# 12V_Buck.net
KiCad netlist of a schematic drawn in Altium Designer
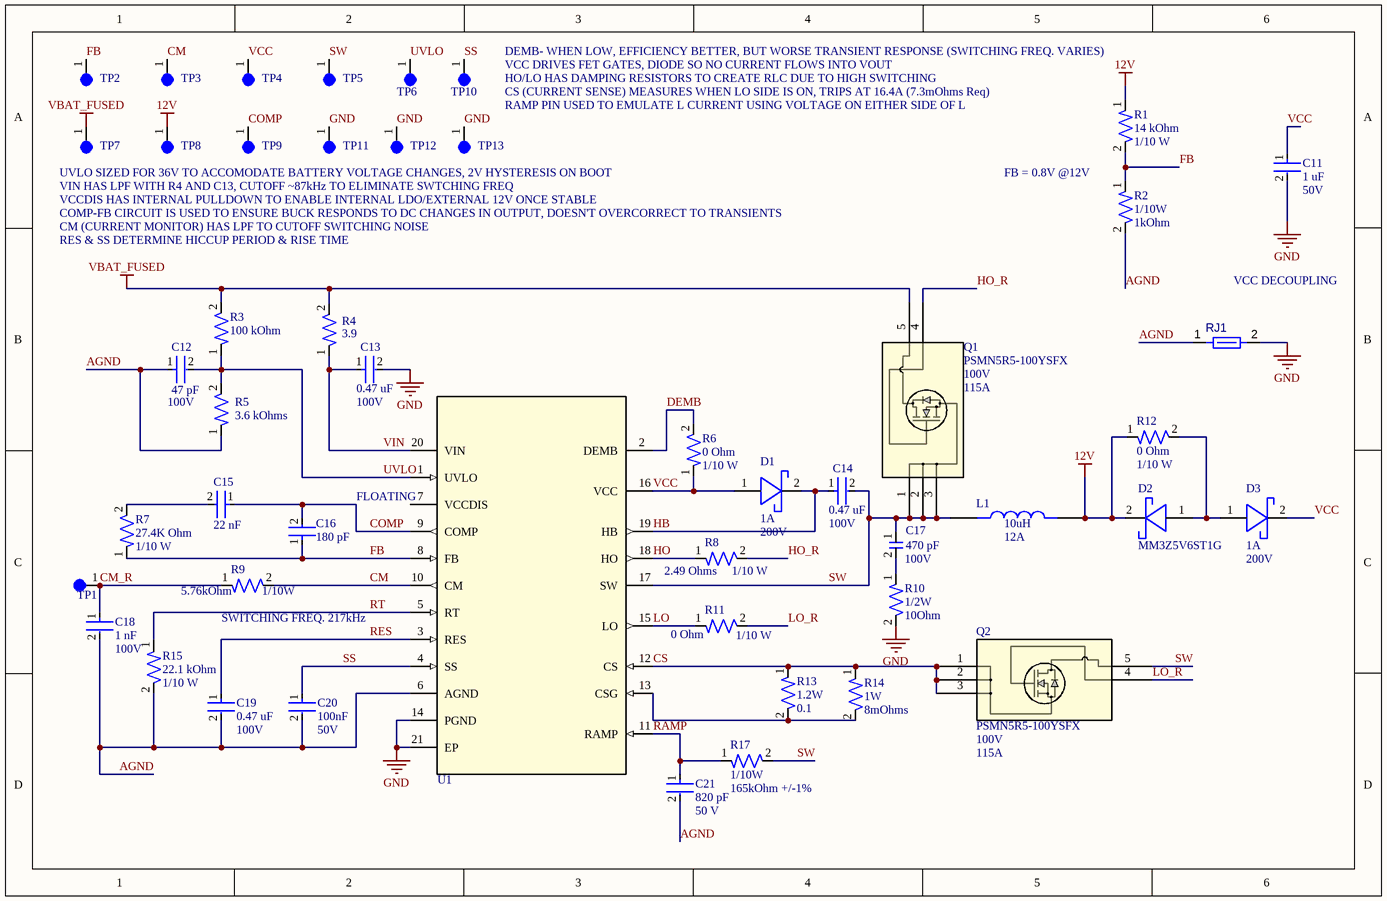
[diagram p0: 12V_Buck.SchDoc]

(export (version "E")
  (design (tool "Eeschema 10.0.6"))
  (components
    (comp (ref "C11")
      (value "UMK107AB7105KA-T")
      (footprint "CAP-0603")
      (description "1 µF ±10% 50V Ceramic Capacitor X7R 0603 (1608 Metric)")
      (fields (field (name "CAPACITANCE") "1 uF") (field (name "VOLTAGE") "50V"))
      (libsource (lib "MasterLib") (part "CAP-1U-0002"))
    )
    (comp (ref "C12")
      (value "7447798111")
      (footprint "CAP-0603")
      (description "47 pF ±5% 100V Ceramic Capacitor C0G, NP0 0603 (1608 Metric)")
      (fields (field (name "CAPACITANCE") "47 pF") (field (name "VOLTAGE RATING") "100V"))
      (libsource (lib "MasterLib") (part "CAP-47P-0001"))
    )
    (comp (ref "C13")
      (value "KAM21KR72A474KL")
      (footprint "CAP-0805")
      (description "0.47 µF ±10% 100V Ceramic Capacitor X7R 0805 (2012 Metric)")
      (fields
        (field (name "TOLERANCE") "+/- 10%")
        (field (name "CAPACITANCE") "0.47 uF")
        (field (name "VOLTAGE") "100V")
      )
      (libsource (lib "MasterLib") (part "CAP-0.47U-0001"))
    )
    (comp (ref "C14")
      (value "KAM21KR72A474KL")
      (footprint "CAP-0805")
      (description "0.47 µF ±10% 100V Ceramic Capacitor X7R 0805 (2012 Metric)")
      (fields
        (field (name "TOLERANCE") "+/- 10%")
        (field (name "CAPACITANCE") "0.47 uF")
        (field (name "VOLTAGE") "100V")
      )
      (libsource (lib "MasterLib") (part "CAP-0.47U-0001"))
    )
    (comp (ref "C15")
      (value "C0603C223K3RAC7867")
      (footprint "CAP-0603")
      (description "0.022 µF ±10% 25V Ceramic Capacitor X7R 0603 (1608 Metric)")
      (fields (field (name "CAPACITANCE") "22 nF"))
      (libsource (lib "MasterLib") (part "CAP-22N-0001"))
    )
    (comp (ref "C16")
      (value "CC0603JRNPO9BN181")
      (footprint "CAP-0603")
      (description "180 pF ±5% 50V Ceramic Capacitor C0G, NP0 0603 (1608 Metric)")
      (fields
        (field (name "TOLERANCE") "+/- 10%")
        (field (name "CAPACITANCE") "180 pF")
        (field (name "VOLTAGE") "50V")
      )
      (libsource (lib "MasterLib") (part "CAP-180P-0001"))
    )
    (comp (ref "C17")
      (value "0603B471K101CT")
      (footprint "CAP-0603")
      (description "470 pF ±10% 100V Ceramic Capacitor X7R 0603 (1608 Metric)")
      (fields
        (field (name "TOLERANCE") "10%")
        (field (name "CAPACITANCE") "470 pF")
        (field (name "VOLTAGE") "100V")
      )
      (libsource (lib "MasterLib") (part "CAP-470P-0001"))
    )
    (comp (ref "C18")
      (value "C0603Y102K1RAC7867")
      (footprint "CAP-0603")
      (description "1000 pF ±10% 100V Ceramic Capacitor X7R 0603 (1608 Metric)")
      (fields (field (name "CAPACITANCE") "1 nF") (field (name "VOLTAGE") "100V"))
      (libsource (lib "MasterLib") (part "CAP-1N-0001"))
    )
    (comp (ref "C19")
      (value "KAM21KR72A474KL")
      (footprint "CAP-0805")
      (description "0.47 µF ±10% 100V Ceramic Capacitor X7R 0805 (2012 Metric)")
      (fields
        (field (name "TOLERANCE") "+/- 10%")
        (field (name "CAPACITANCE") "0.47 uF")
        (field (name "VOLTAGE") "100V")
      )
      (libsource (lib "MasterLib") (part "CAP-0.47U-0001"))
    )
    (comp (ref "C20")
      (value "CC0603KRX7R9BB104")
      (footprint "CAP-0603")
      (description "0.1 µF ±10% 50V Ceramic Capacitor X7R 0603 (1608 Metric)")
      (fields
        (field (name "MANUFACTURER PART NUMBER") "CC0603KRX7R0BB104")
        (field (name "MANUFACTURER") "YAGEO")
        (field (name "CAPACITANCE") "100nF")
        (field (name "VOLTAGE RATING") "50V")
      )
      (libsource (lib "MasterLib") (part "CAP-100N-0001"))
    )
    (comp (ref "C21")
      (value "C0603C821K5RACTU")
      (footprint "CAP-0603")
      (description "820 pF ±10% 50V Ceramic Capacitor X7R 0603 (1608 Metric)")
      (fields (field (name "CAPACITANCE") "820 pF") (field (name "VOLTAGE") "50 V"))
      (libsource (lib "JLC_25") (part "CAP-820P-0001"))
    )
    (comp (ref "D1")
      (value "SS1200")
      (footprint "SMA_DIO")
      (description "DIODE SCHOTTKY 200V 1A SMA")
      (fields (field (name "CURRENT RATING") "1A") (field (name "REVERSE VOLTAGE") "200V"))
      (libsource (lib "JLC_25") (part "DIO-SCHOTTKY-0004"))
    )
    (comp (ref "D2")
      (value "MM3Z5V6ST1G")
      (footprint "DIO_MM3Z3V0T1G - duplicate")
      (libsource (lib "MasterLib") (part "TESTDIOZ"))
    )
    (comp (ref "D3")
      (value "SS1200")
      (footprint "SMA_DIO")
      (description "DIODE SCHOTTKY 200V 1A SMA")
      (fields (field (name "CURRENT RATING") "1A") (field (name "REVERSE VOLTAGE") "200V"))
      (libsource (lib "JLC_25") (part "DIO-SCHOTTKY-0004"))
    )
    (comp (ref "L1")
      (value "10uH")
      (footprint "IND_SRP1265_BRN")
      (description "10 µH Shielded Inductor 12 A 16.5mOhm Max Nonstandard")
      (fields
        (field (name "MP") "SRP1265A-100M")
        (field (name "CURRENT") "12A")
        (field (name "Comment") "SRP1265WA-100M")
      )
      (libsource (lib "MasterLib") (part "IND-10U-0002"))
    )
    (comp (ref "Q1")
      (value "PSMN5R5-100YSFX")
      (footprint "LFPAK_SOT669_NEX")
      (description "N-Channel 100 V 115A (Tc) 238W (Tc) Surface Mount LFPAK56, Power-SO8")
      (fields
        (field (name "MANUFACTURER_PART_NUMBER") "TPH2R506PL")
        (field (name "VDSS") "100V")
        (field (name "DRAIN CURRENT") "115A")
      )
      (libsource (lib "") (part "NMOS-115A-0001_1"))
    )
    (comp (ref "Q2")
      (value "PSMN5R5-100YSFX")
      (footprint "LFPAK_SOT669_NEX")
      (description "N-Channel 100 V 115A (Tc) 238W (Tc) Surface Mount LFPAK56, Power-SO8")
      (fields
        (field (name "MANUFACTURER_PART_NUMBER") "TPH2R506PL")
        (field (name "VDSS") "100V")
        (field (name "DRAIN CURRENT") "115A")
      )
      (libsource (lib "MasterLib") (part "NMOS-115A-0001"))
    )
    (comp (ref "R1")
      (value "RC0603FR-0714KL")
      (footprint "RES-0603")
      (description "14 kOhms ±1% 0.1W, 1/10W Chip Resistor 0603 (1608 Metric) Moisture Resistant Thick Film")
      (fields
        (field (name "TOLERANCE") "+/- 1%")
        (field (name "RESISTANCE") "14 kOhm")
        (field (name "POWER") "1/10 W")
      )
      (libsource (lib "MasterLib") (part "RES-14K-0001"))
    )
    (comp (ref "R2")
      (value "RT0603FRE131KL")
      (footprint "RES-0603")
      (description "1 kOhms ±1% 0.1W, 1/10W Chip Resistor 0603 (1608 Metric) Thin Film")
      (fields
        (field (name "MANUFACTURER") "YAGEO")
        (field (name "POWER RATING") "1/10W")
        (field (name "RESISTANCE") "1kOhm")
      )
      (libsource (lib "MasterLib") (part "RES-1K-0002"))
    )
    (comp (ref "R3")
      (value "RC0603FR-07100KL")
      (footprint "RES-0603")
      (description "100 kOhms ±1% 0.1W, 1/10W Chip Resistor 0603 (1608 Metric) Moisture Resistant Thick Film")
      (fields
        (field (name "TOLERANCE") "+/- 1%")
        (field (name "RESISTANCE") "100 kOhm")
        (field (name "POWER") "1/10 W")
      )
      (libsource (lib "MasterLib") (part "RES-100K-0003"))
    )
    (comp (ref "R4")
      (value "RC0805FR-073R9L")
      (footprint "RES-0805")
      (description "3.9 Ohms ±1% 0.125W, 1/8W Chip Resistor 0805 (2012 Metric) Moisture Resistant Thick Film")
      (fields (field (name "PARAMETER 1") "3.9"))
      (libsource (lib "MasterLib") (part "RES-3.9-0001"))
    )
    (comp (ref "R5")
      (value "RC0603FR-073K6L")
      (footprint "RES-0603")
      (description "3.6 kOhms ±1% 0.1W, 1/10W Chip Resistor 0603 (1608 Metric) Moisture Resistant Thick Film")
      (fields (field (name "RESISTANCE") "3.6 kOhms") (field (name "POWER") "1/10 W"))
      (libsource (lib "MasterLib") (part "RES-3.6K-0001"))
    )
    (comp (ref "R6")
      (value "RMCF0603ZT0R00")
      (footprint "RES-0603")
      (description "0 Ohms Jumper 0.1W, 1/10W Chip Resistor 0603 (1608 Metric) Automotive AEC-Q200 Thick Film")
      (fields (field (name "RESISTANCE") "0 Ohm") (field (name "POWER") "1/10 W"))
      (libsource (lib "MasterLib") (part "RES-0-0001"))
    )
    (comp (ref "R7")
      (value "RC0603FR-0727K4L")
      (footprint "RES-0603")
      (description "27.4 kOhms ±1% 0.1W, 1/10W Chip Resistor 0603 (1608 Metric) Moisture Resistant Thick Film")
      (fields
        (field (name "JLC PART NUMBER") "C144778")
        (field (name "RESISTANCE") "27.4K Ohm")
        (field (name "POWER") "1/10 W")
      )
      (libsource (lib "MasterLib") (part "RES-27.4K-0001"))
    )
    (comp (ref "R8")
      (value "RC0603FR-072R49L")
      (footprint "RES-0603")
      (description "2.49 Ohms ±1% 0.1W, 1/10W Chip Resistor 0603 (1608 Metric) Moisture Resistant Thick Film")
      (fields (field (name "POWER") "1/10 W") (field (name "RESISTANCE") "2.49 Ohms"))
      (libsource (lib "MasterLib") (part "RES-2.49-0001"))
    )
    (comp (ref "R9")
      (value "ARG03FTC5761")
      (footprint "RES-0603")
      (fields
        (field (name "MANUFACTURER") "Viking Tech")
        (field (name "POWER RATING") "1/10W")
        (field (name "RESISTANCE") "5.76kOhm")
      )
      (libsource (lib "MasterLib") (part "RES-5.76K-0001"))
    )
    (comp (ref "R10")
      (value "SG73P1JTTD100J")
      (footprint "RES-0603")
      (fields
        (field (name "MANUFACTURER PART NUMBER") "RC0603FR-0710KP")
        (field (name "MANUFACTURER") "Vishay")
        (field (name "POWER RATING") "1/2W")
        (field (name "RESISTANCE") "10Ohm")
      )
      (libsource (lib "MasterLib") (part "RES-10-0001"))
    )
    (comp (ref "R11")
      (value "RMCF0603ZT0R00")
      (footprint "RES-0603")
      (description "0 Ohms Jumper 0.1W, 1/10W Chip Resistor 0603 (1608 Metric) Automotive AEC-Q200 Thick Film")
      (fields (field (name "RESISTANCE") "0 Ohm") (field (name "POWER") "1/10 W"))
      (libsource (lib "MasterLib") (part "RES-0-0001"))
    )
    (comp (ref "R12")
      (value "RMCF0603ZT0R00")
      (footprint "RES-0603")
      (description "0 Ohms Jumper 0.1W, 1/10W Chip Resistor 0603 (1608 Metric) Automotive AEC-Q200 Thick Film")
      (fields (field (name "RESISTANCE") "0 Ohm") (field (name "POWER") "1/10 W"))
      (libsource (lib "MasterLib") (part "RES-0-0001"))
    )
    (comp (ref "R13")
      (value "PE0508FRE070R1L")
      (footprint "RES-0805")
      (fields (field (name "POWER") "1.2W") (field (name "RESISTANCE") "0.1"))
      (libsource (lib "MasterLib") (part "RES-0.1-0001"))
    )
    (comp (ref "R14")
      (value "PE1206FKM470R008Z")
      (footprint "RES-1206")
      (description "8 mOhms ±1% 1W Chip Resistor 1206 (3216 Metric) Current Sense Metal Foil")
      (fields (field (name "POWER") "1W") (field (name "RESISTANCE") "8mOhms"))
      (libsource (lib "MasterLib") (part "RES-8mOhms-0001"))
    )
    (comp (ref "R15")
      (value "RC0603FR-0722K1L")
      (footprint "RES-0603")
      (description "22.1 kOhms ±1% 0.1W, 1/10W Chip Resistor 0603 (1608 Metric) Moisture Resistant Thick Film")
      (fields
        (field (name "TOLERANCE") "1%")
        (field (name "RESISTANCE") "22.1 kOhm")
        (field (name "POWER") "1/10 W")
      )
      (libsource (lib "MasterLib") (part "RES-22.1K-0001"))
    )
    (comp (ref "R17")
      (value "RC0603FR-07165KL")
      (footprint "RES-0603")
      (description "165k Ohms ±1% 0.1W, 1/10W Chip Resistor 0603 (1608 Metric) Moisture Resistant Thick Film")
      (fields
        (field (name "MANUFACTURER") "YAGEO")
        (field (name "POWER RATING") "1/10W")
        (field (name "RESISTANCE") "165kOhm +/-1%")
      )
      (libsource (lib "MasterLib") (part "RES-165K-0001"))
    )
    (comp (ref "RJ1")
      (value "Net Tie 12x8mil")
      (footprint "SHORT06-FP")
      (libsource (lib "Altium 365 Cloud") (part "CMP-00022-00002-2"))
    )
    (comp (ref "TP1")
      (value "5003")
      (footprint "TEST-POINT-0001")
      (description "Oranange PC Test Point, Miniature Phoisphor Bronze Silver Plating Through Hole Mounting Type")
      (libsource (lib "JLC_25") (part "TEST-POINT-0001"))
    )
    (comp (ref "TP2")
      (value "5003")
      (footprint "TEST-POINT-0001")
      (description "Oranange PC Test Point, Miniature Phoisphor Bronze Silver Plating Through Hole Mounting Type")
      (libsource (lib "JLC_25") (part "TEST-POINT-0001"))
    )
    (comp (ref "TP3")
      (value "5003")
      (footprint "TEST-POINT-0001")
      (description "Oranange PC Test Point, Miniature Phoisphor Bronze Silver Plating Through Hole Mounting Type")
      (libsource (lib "JLC_25") (part "TEST-POINT-0001"))
    )
    (comp (ref "TP4")
      (value "5003")
      (footprint "TEST-POINT-0001")
      (description "Oranange PC Test Point, Miniature Phoisphor Bronze Silver Plating Through Hole Mounting Type")
      (libsource (lib "JLC_25") (part "TEST-POINT-0001"))
    )
    (comp (ref "TP5")
      (value "5003")
      (footprint "TEST-POINT-0001")
      (description "Oranange PC Test Point, Miniature Phoisphor Bronze Silver Plating Through Hole Mounting Type")
      (libsource (lib "JLC_25") (part "TEST-POINT-0001"))
    )
    (comp (ref "TP6")
      (value "5003")
      (footprint "TEST-POINT-0001")
      (description "Oranange PC Test Point, Miniature Phoisphor Bronze Silver Plating Through Hole Mounting Type")
      (libsource (lib "JLC_25") (part "TEST-POINT-0001"))
    )
    (comp (ref "TP7")
      (value "5003")
      (footprint "TEST-POINT-0001")
      (description "Oranange PC Test Point, Miniature Phoisphor Bronze Silver Plating Through Hole Mounting Type")
      (libsource (lib "JLC_25") (part "TEST-POINT-0001"))
    )
    (comp (ref "TP8")
      (value "5003")
      (footprint "TEST-POINT-0001")
      (description "Oranange PC Test Point, Miniature Phoisphor Bronze Silver Plating Through Hole Mounting Type")
      (libsource (lib "JLC_25") (part "TEST-POINT-0001"))
    )
    (comp (ref "TP9")
      (value "5003")
      (footprint "TEST-POINT-0001")
      (description "Oranange PC Test Point, Miniature Phoisphor Bronze Silver Plating Through Hole Mounting Type")
      (libsource (lib "JLC_25") (part "TEST-POINT-0001"))
    )
    (comp (ref "TP10")
      (value "5003")
      (footprint "TEST-POINT-0001")
      (description "Oranange PC Test Point, Miniature Phoisphor Bronze Silver Plating Through Hole Mounting Type")
      (libsource (lib "JLC_25") (part "TEST-POINT-0001"))
    )
    (comp (ref "TP11")
      (value "5003")
      (footprint "TEST-POINT-0001")
      (description "Oranange PC Test Point, Miniature Phoisphor Bronze Silver Plating Through Hole Mounting Type")
      (libsource (lib "JLC_25") (part "TEST-POINT-0001"))
    )
    (comp (ref "TP12")
      (value "5003")
      (footprint "TEST-POINT-0001")
      (description "Oranange PC Test Point, Miniature Phoisphor Bronze Silver Plating Through Hole Mounting Type")
      (libsource (lib "JLC_25") (part "TEST-POINT-0001"))
    )
    (comp (ref "TP13")
      (value "5003")
      (footprint "TEST-POINT-0001")
      (description "Oranange PC Test Point, Miniature Phoisphor Bronze Silver Plating Through Hole Mounting Type")
      (libsource (lib "JLC_25") (part "TEST-POINT-0001"))
    )
    (comp (ref "U1")
      (value "LM5117PMHX/NOPB")
      (footprint "IC-20-HTSSOP")
      (description "Buck Regulator Positive Output Step-Down DC-DC Controller IC 20-HTSSOP")
      (fields
        (field (name "MANUFACTURER PART NUMBER") "TPS62933ODRLR")
        (field (name "MANUFACTURER") "Texas Instruments")
      )
      (libsource (lib "MasterLib") (part "IC-BUCK-0011"))
    )
  )
  (nets
    (net (code "1") (name "/AGND") (class "Default")
      (node (ref "C12") (pin "1") (pinfunction "1_1") (pintype "passive"))
      (node (ref "C18") (pin "2") (pinfunction "2_2") (pintype "passive"))
      (node (ref "C19") (pin "2") (pinfunction "2_2") (pintype "passive"))
      (node (ref "C20") (pin "2") (pinfunction "2_2") (pintype "passive"))
      (node (ref "C21") (pin "2") (pinfunction "2_2") (pintype "passive"))
      (node (ref "R15") (pin "2") (pinfunction "2_2") (pintype "passive"))
      (node (ref "R2") (pin "2") (pinfunction "2_2") (pintype "passive"))
      (node (ref "R5") (pin "1") (pinfunction "1_1") (pintype "passive"))
      (node (ref "RJ1") (pin "1") (pinfunction "1_1") (pintype "passive"))
      (node (ref "U1") (pin "6") (pinfunction "AGND_6") (pintype "power_in"))
    )
    (net (code "2") (name "/CM") (class "Default")
      (node (ref "R9") (pin "2") (pinfunction "2_2") (pintype "passive"))
      (node (ref "TP3") (pin "1") (pinfunction "0_1") (pintype "passive"))
      (node (ref "U1") (pin "10") (pinfunction "CM_10") (pintype "output"))
    )
    (net (code "3") (name "/CM_R") (class "Default")
      (node (ref "C18") (pin "1") (pinfunction "1_1") (pintype "passive"))
      (node (ref "R9") (pin "1") (pinfunction "1_1") (pintype "passive"))
      (node (ref "TP1") (pin "1") (pinfunction "0_1") (pintype "passive"))
    )
    (net (code "4") (name "/COMP") (class "Default")
      (node (ref "C15") (pin "1") (pinfunction "1_1") (pintype "passive"))
      (node (ref "C16") (pin "2") (pinfunction "2_2") (pintype "passive"))
      (node (ref "TP9") (pin "1") (pinfunction "0_1") (pintype "passive"))
      (node (ref "U1") (pin "9") (pinfunction "COMP_9") (pintype "output"))
    )
    (net (code "5") (name "/CS") (class "Default")
      (node (ref "Q2") (pin "1") (pinfunction "1_1") (pintype "passive"))
      (node (ref "Q2") (pin "2") (pinfunction "2_2") (pintype "passive"))
      (node (ref "Q2") (pin "3") (pinfunction "3_3") (pintype "passive"))
      (node (ref "R13") (pin "1") (pinfunction "1_1") (pintype "passive"))
      (node (ref "R14") (pin "1") (pinfunction "1_1") (pintype "passive"))
      (node (ref "U1") (pin "12") (pinfunction "CS_12") (pintype "input"))
    )
    (net (code "6") (name "/DEMB") (class "Default")
      (node (ref "R6") (pin "2") (pinfunction "2_2") (pintype "passive"))
      (node (ref "U1") (pin "2") (pinfunction "DEMB_2") (pintype "passive"))
    )
    (net (code "7") (name "/FB") (class "Default")
      (node (ref "C16") (pin "1") (pinfunction "1_1") (pintype "passive"))
      (node (ref "R1") (pin "2") (pinfunction "2_2") (pintype "passive"))
      (node (ref "R2") (pin "1") (pinfunction "1_1") (pintype "passive"))
      (node (ref "R7") (pin "1") (pinfunction "1_1") (pintype "passive"))
      (node (ref "TP2") (pin "1") (pinfunction "0_1") (pintype "passive"))
      (node (ref "U1") (pin "8") (pinfunction "FB_8") (pintype "input"))
    )
    (net (code "8") (name "/HB") (class "Default")
      (node (ref "C14") (pin "1") (pinfunction "1_1") (pintype "passive"))
      (node (ref "D1") (pin "2") (pinfunction "ANODE_2") (pintype "passive"))
      (node (ref "U1") (pin "19") (pinfunction "HB_19") (pintype "output"))
    )
    (net (code "9") (name "/HO") (class "Default")
      (node (ref "R8") (pin "1") (pinfunction "1_1") (pintype "passive"))
      (node (ref "U1") (pin "18") (pinfunction "HO_18") (pintype "output"))
    )
    (net (code "10") (name "/HO_R") (class "Default")
      (node (ref "Q1") (pin "4") (pinfunction "4_4") (pintype "passive"))
      (node (ref "R8") (pin "2") (pinfunction "2_2") (pintype "passive"))
    )
    (net (code "11") (name "/LO") (class "Default")
      (node (ref "R11") (pin "1") (pinfunction "1_1") (pintype "passive"))
      (node (ref "U1") (pin "15") (pinfunction "LO_15") (pintype "output"))
    )
    (net (code "12") (name "/LO_R") (class "Default")
      (node (ref "Q2") (pin "4") (pinfunction "4_4") (pintype "passive"))
      (node (ref "R11") (pin "2") (pinfunction "2_2") (pintype "passive"))
    )
    (net (code "13") (name "/RAMP") (class "Default")
      (node (ref "C21") (pin "1") (pinfunction "1_1") (pintype "passive"))
      (node (ref "R17") (pin "1") (pinfunction "1_1") (pintype "passive"))
      (node (ref "U1") (pin "11") (pinfunction "RAMP_11") (pintype "input"))
    )
    (net (code "14") (name "/RES") (class "Default")
      (node (ref "C19") (pin "1") (pinfunction "1_1") (pintype "passive"))
      (node (ref "U1") (pin "3") (pinfunction "RES_3") (pintype "input"))
    )
    (net (code "15") (name "/RT") (class "Default")
      (node (ref "R15") (pin "1") (pinfunction "1_1") (pintype "passive"))
      (node (ref "U1") (pin "5") (pinfunction "RT_5") (pintype "input"))
    )
    (net (code "16") (name "/SS") (class "Default")
      (node (ref "C20") (pin "1") (pinfunction "1_1") (pintype "passive"))
      (node (ref "TP10") (pin "1") (pinfunction "0_1") (pintype "passive"))
      (node (ref "U1") (pin "4") (pinfunction "SS_4") (pintype "input"))
    )
    (net (code "17") (name "/SW") (class "Default")
      (node (ref "C14") (pin "2") (pinfunction "2_2") (pintype "passive"))
      (node (ref "C17") (pin "1") (pinfunction "1_1") (pintype "passive"))
      (node (ref "L1") (pin "1") (pinfunction "1_1") (pintype "passive"))
      (node (ref "Q1") (pin "1") (pinfunction "1_1") (pintype "passive"))
      (node (ref "Q1") (pin "2") (pinfunction "2_2") (pintype "passive"))
      (node (ref "Q1") (pin "3") (pinfunction "3_3") (pintype "passive"))
      (node (ref "Q2") (pin "5") (pinfunction "5_5") (pintype "passive"))
      (node (ref "R17") (pin "2") (pinfunction "2_2") (pintype "passive"))
      (node (ref "TP5") (pin "1") (pinfunction "0_1") (pintype "passive"))
      (node (ref "U1") (pin "17") (pinfunction "SW_17") (pintype "power_in"))
    )
    (net (code "18") (name "/UVLO") (class "Default")
      (node (ref "C12") (pin "2") (pinfunction "2_2") (pintype "passive"))
      (node (ref "R3") (pin "1") (pinfunction "1_1") (pintype "passive"))
      (node (ref "R5") (pin "2") (pinfunction "2_2") (pintype "passive"))
      (node (ref "TP6") (pin "1") (pinfunction "0_1") (pintype "passive"))
      (node (ref "U1") (pin "1") (pinfunction "UVLO_1") (pintype "input"))
    )
    (net (code "19") (name "/VCC") (class "Default")
      (node (ref "C11") (pin "1") (pinfunction "1_1") (pintype "passive"))
      (node (ref "D1") (pin "1") (pinfunction "CATHODE_1") (pintype "passive"))
      (node (ref "D3") (pin "2") (pinfunction "ANODE_2") (pintype "passive"))
      (node (ref "R6") (pin "1") (pinfunction "1_1") (pintype "passive"))
      (node (ref "TP4") (pin "1") (pinfunction "0_1") (pintype "passive"))
      (node (ref "U1") (pin "16") (pinfunction "VCC_16") (pintype "power_in"))
    )
    (net (code "20") (name "/VIN") (class "Default")
      (node (ref "C13") (pin "1") (pinfunction "1_1") (pintype "passive"))
      (node (ref "R4") (pin "1") (pinfunction "1_1") (pintype "passive"))
      (node (ref "U1") (pin "20") (pinfunction "VIN_20") (pintype "power_in"))
    )
    (net (code "21") (name "12V") (class "Default")
      (node (ref "D2") (pin "2") (pinfunction "6_2") (pintype "passive"))
      (node (ref "L1") (pin "2") (pinfunction "2_2") (pintype "passive"))
      (node (ref "R1") (pin "1") (pinfunction "1_1") (pintype "passive"))
      (node (ref "R12") (pin "1") (pinfunction "1_1") (pintype "passive"))
      (node (ref "TP8") (pin "1") (pinfunction "0_1") (pintype "passive"))
    )
    (net (code "22") (name "GND") (class "Default")
      (node (ref "C11") (pin "2") (pinfunction "2_2") (pintype "passive"))
      (node (ref "C13") (pin "2") (pinfunction "2_2") (pintype "passive"))
      (node (ref "R10") (pin "2") (pinfunction "2_2") (pintype "passive"))
      (node (ref "RJ1") (pin "2") (pinfunction "2_2") (pintype "passive"))
      (node (ref "TP11") (pin "1") (pinfunction "0_1") (pintype "passive"))
      (node (ref "TP12") (pin "1") (pinfunction "0_1") (pintype "passive"))
      (node (ref "TP13") (pin "1") (pinfunction "0_1") (pintype "passive"))
      (node (ref "U1") (pin "14") (pinfunction "PGND_14") (pintype "power_in"))
      (node (ref "U1") (pin "21") (pinfunction "EP_21") (pintype "passive"))
    )
    (net (code "23") (name "Net-(C15-Pad2)") (class "Default")
      (node (ref "C15") (pin "2") (pinfunction "2_2") (pintype "passive"))
      (node (ref "R7") (pin "2") (pinfunction "2_2") (pintype "passive"))
    )
    (net (code "24") (name "Net-(C17-Pad2)") (class "Default")
      (node (ref "C17") (pin "2") (pinfunction "2_2") (pintype "passive"))
      (node (ref "R10") (pin "1") (pinfunction "1_1") (pintype "passive"))
    )
    (net (code "25") (name "Net-(D2-5)") (class "Default")
      (node (ref "D2") (pin "1") (pinfunction "5_1") (pintype "passive"))
      (node (ref "D3") (pin "1") (pinfunction "CATHODE_1") (pintype "passive"))
      (node (ref "R12") (pin "2") (pinfunction "2_2") (pintype "passive"))
    )
    (net (code "26") (name "Net-(U1-CSG)") (class "Default")
      (node (ref "R13") (pin "2") (pinfunction "2_2") (pintype "passive"))
      (node (ref "R14") (pin "2") (pinfunction "2_2") (pintype "passive"))
      (node (ref "U1") (pin "13") (pinfunction "CSG_13") (pintype "input"))
    )
    (net (code "27") (name "VBAT_FUSED") (class "Default")
      (node (ref "Q1") (pin "5") (pinfunction "5_5") (pintype "passive"))
      (node (ref "R3") (pin "2") (pinfunction "2_2") (pintype "passive"))
      (node (ref "R4") (pin "2") (pinfunction "2_2") (pintype "passive"))
      (node (ref "TP7") (pin "1") (pinfunction "0_1") (pintype "passive"))
    )
    (net (code "28") (name "unconnected-(U1-VCCDIS-Pad7)") (class "Default")
      (node (ref "U1") (pin "7") (pinfunction "VCCDIS_7") (pintype "passive"))
    )
  )
)
